# PDU.net
KiCad netlist of a schematic drawn in Altium Designer
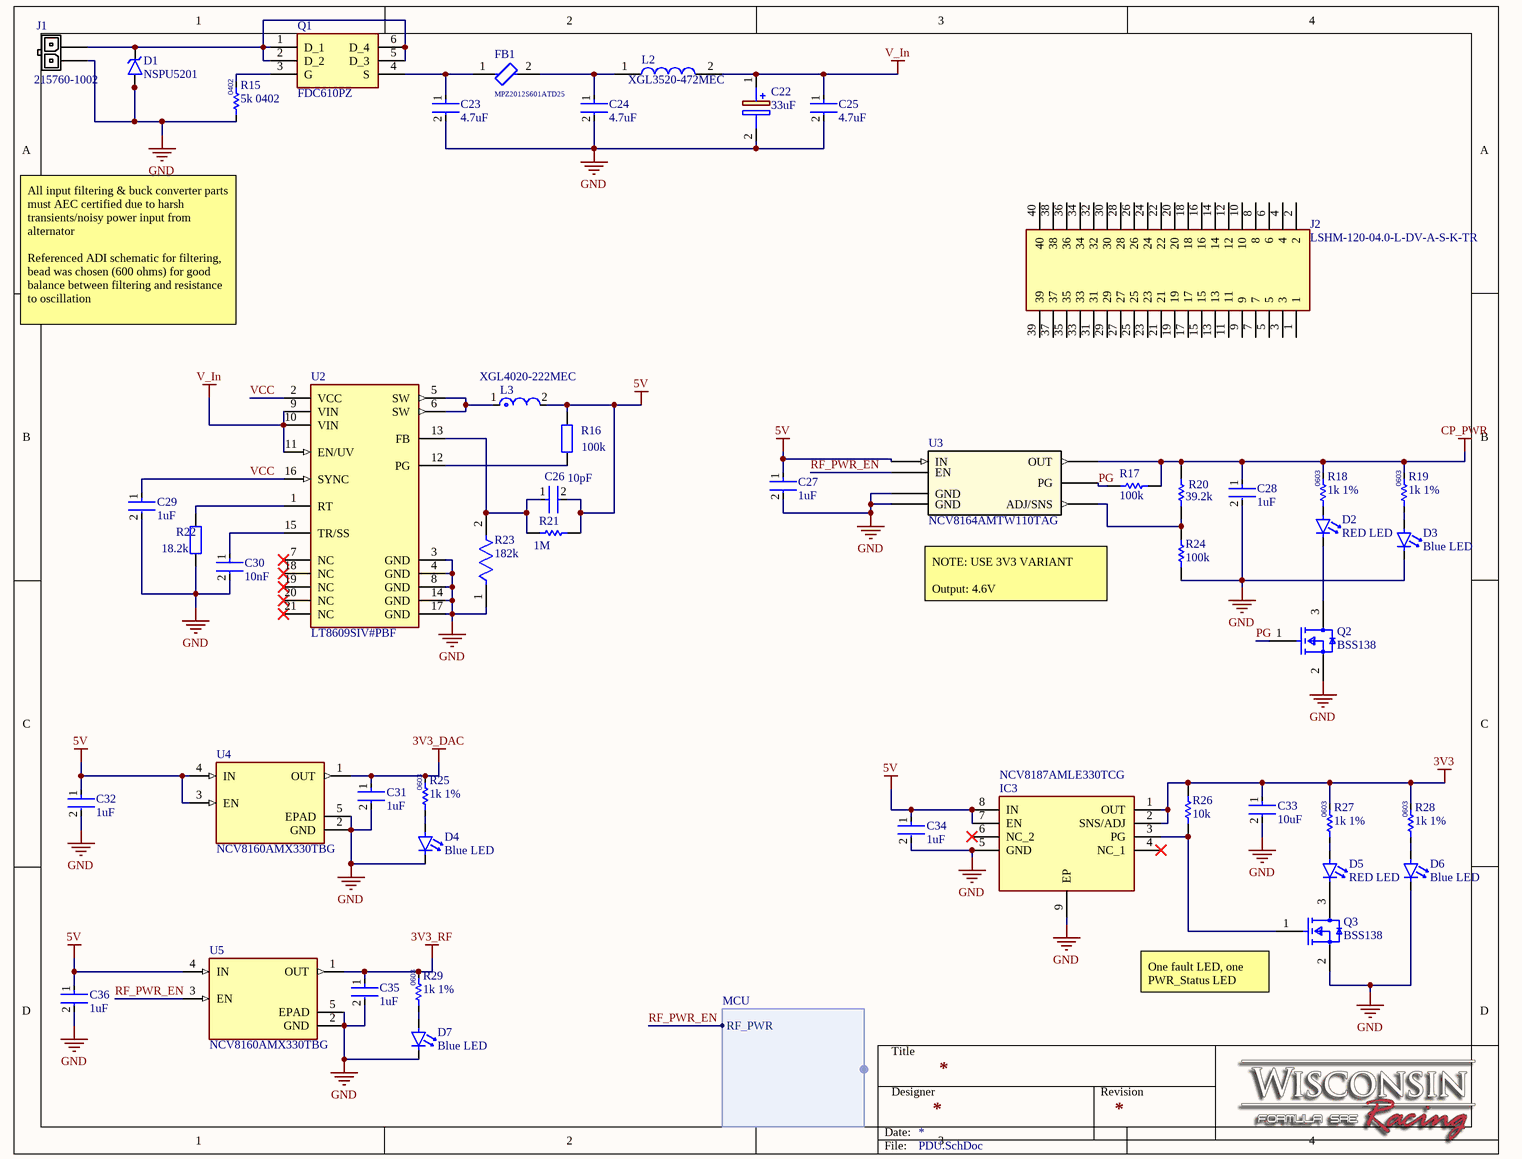
[diagram p0: PDU.SchDoc]

(export (version "E")
  (design (tool "Eeschema 10.0.6"))
  (components
    (comp (ref "C22")
      (value "33uF")
      (footprint "SamacSys:MAL215097904E3")
      (description "Capacitor Polarised\r\n\r\nMAL215097904E3")
      (fields
        (field (name "MANUFACTURER_PART_NUMBER") "MAL215097904E3")
        (field (name "MOUSER PART NUMBER") "594-MAL215097904E3")
      )
      (libsource (lib "*") (part "MAL215097904E3"))
    )
    (comp (ref "C23")
      (value "4.7uF")
      (footprint "FP-CGA4J-IPC_C")
      (description "Cap Ceramic 4.7uF 50V X7R 10% Pad SMD 0805 +125°C Automotive T/R")
      (libsource (lib "Altium Content Vault") (part "b4654b650e69147ec39a6b967a45e02"))
    )
    (comp (ref "C24")
      (value "4.7uF")
      (footprint "FP-CGA4J-IPC_C")
      (description "Cap Ceramic 4.7uF 50V X7R 10% Pad SMD 0805 +125°C Automotive T/R")
      (libsource (lib "Altium Content Vault") (part "b4654b650e69147ec39a6b967a45e02"))
    )
    (comp (ref "C25")
      (value "4.7uF")
      (footprint "FP-CGA4J-IPC_C")
      (description "Cap Ceramic 4.7uF 50V X7R 10% Pad SMD 0805 +125°C Automotive T/R")
      (libsource (lib "Altium Content Vault") (part "b4654b650e69147ec39a6b967a45e02"))
    )
    (comp (ref "C26")
      (value "10pF")
      (footprint "FP-GCM155-0_05-IPC_C")
      (description "Ceramic Capacitor for Automotive 10pF ±5% 50VDC C0G 0402 Paper T/R")
      (fields (field (name "TOLERANCE") "5%"))
      (libsource (lib "Altium Content Vault") (part "02cd4be3c70576c341d710602a673aa"))
    )
    (comp (ref "C27")
      (value "1uF")
      (footprint "FP-GRM155-0_1-IPC_C")
      (libsource (lib "Altium Content Vault") (part "11868f565c42a9108669ba33697ecf6"))
    )
    (comp (ref "C28")
      (value "1uF")
      (footprint "FP-GRM155-0_1-IPC_C")
      (libsource (lib "Altium Content Vault") (part "11868f565c42a9108669ba33697ecf6"))
    )
    (comp (ref "C29")
      (value "1uF")
      (footprint "FP-GRT155-0_1-IPC_A")
      (description "Multi-Layer Ceramic Capacitor 1uF 25V X6S ±10% 0402 Paper T/R\r\n\r\nGRT155C81E105KE13D")
      (libsource (lib "Altium Content Vault") (part "02cd4be3c70576c341d710602a673aa"))
    )
    (comp (ref "C30")
      (value "10nF")
      (footprint "FP-GCM155-0_05-IPC_C")
      (description "Ceramic Capacitor for Automotive 10nF ±10% 50VDC X7R 0402 Paper T/R\r\n\r\nGCM155R71H103KA55D")
      (fields (field (name "TOLERANCE") "10%") (field (name "VOLTAGE") "50V"))
      (libsource (lib "Altium Content Vault") (part "02cd4be3c70576c341d710602a673aa"))
    )
    (comp (ref "C31")
      (value "1uF")
      (footprint "FP-GRM155-0_1-IPC_C")
      (libsource (lib "Altium Content Vault") (part "11868f565c42a9108669ba33697ecf6"))
    )
    (comp (ref "C32")
      (value "1uF")
      (footprint "FP-GRM155-0_1-IPC_C")
      (libsource (lib "Altium Content Vault") (part "11868f565c42a9108669ba33697ecf6"))
    )
    (comp (ref "C33")
      (value "10uF")
      (footprint "FP-GRM155-0_2-IPC_A")
      (description "Chip Multilayer Ceramic Capacitors for General Purpose, 0402, 10uF, X5R, 15%, 20%, 6.3V")
      (libsource (lib "Altium Content Vault") (part "b4654b650e69147ec39a6b967a45e02"))
    )
    (comp (ref "C34")
      (value "1uF")
      (footprint "FP-GRM155-0_1-IPC_C")
      (libsource (lib "Altium Content Vault") (part "11868f565c42a9108669ba33697ecf6"))
    )
    (comp (ref "C35")
      (value "1uF")
      (footprint "FP-GRM155-0_1-IPC_C")
      (libsource (lib "Altium Content Vault") (part "11868f565c42a9108669ba33697ecf6"))
    )
    (comp (ref "C36")
      (value "1uF")
      (footprint "FP-GRM155-0_1-IPC_C")
      (libsource (lib "Altium Content Vault") (part "11868f565c42a9108669ba33697ecf6"))
    )
    (comp (ref "D1")
      (value "NSPU5201")
      (footprint "NSPM5131MUTBG")
      (fields
        (field (name "ARROW PART NUMBER") "NSPU5201MUTBG")
        (field (name "MOUSER PART NUMBER") "863-NSPU5201MUTBG")
      )
      (libsource (lib "University of Wisconsin Formula FSAE") (part "NSPU5201MUTBG"))
    )
    (comp (ref "D2")
      (value "RED LED")
      (footprint "DIOC1608X05N")
      (description "0603 Red SMD Led")
      (libsource (lib "University of Wisconsin Formula FSAE") (part "L196L-LIC-Symbol-1"))
    )
    (comp (ref "D3")
      (value "Blue LED")
      (footprint "0603-LED-1")
      (description "Single Color LED, Blue, Water Clear, 1.1mm")
      (libsource (lib "University of Wisconsin Formula FSAE") (part "LED"))
    )
    (comp (ref "D4")
      (value "Blue LED")
      (footprint "0603-LED-1")
      (description "Single Color LED, Blue, Water Clear, 1.1mm")
      (libsource (lib "University of Wisconsin Formula FSAE") (part "LED"))
    )
    (comp (ref "D5")
      (value "RED LED")
      (footprint "DIOC1608X05N")
      (description "0603 Red SMD Led")
      (libsource (lib "University of Wisconsin Formula FSAE") (part "L196L-LIC-Symbol-1"))
    )
    (comp (ref "D6")
      (value "Blue LED")
      (footprint "0603-LED-1")
      (description "Single Color LED, Blue, Water Clear, 1.1mm")
      (libsource (lib "University of Wisconsin Formula FSAE") (part "LED"))
    )
    (comp (ref "D7")
      (value "Blue LED")
      (footprint "0603-LED-1")
      (description "Single Color LED, Blue, Water Clear, 1.1mm")
      (libsource (lib "University of Wisconsin Formula FSAE") (part "LED"))
    )
    (comp (ref "FB1")
      (value "MPZ2012S601ATD25")
      (footprint "BEADC2012X105N")
      (description "Ferrite Beads Multi-Layer Power 600Ohm 25% 100MHz 2A 100mOhm DCR 0805 Automotive T/R")
      (fields (field (name "MOUSER PART NUMBER") "810-MPZ2012S601ATD25"))
      (libsource (lib "University of Wisconsin Formula FSAE") (part "MPZ2012S601ATD25"))
    )
    (comp (ref "IC3")
      (value "NCV8187AMLE330TCG")
      (footprint "SamacSys:SON65P300X300X100-9N-D")
      (description "Integrated Circuit")
      (fields (field (name "MOUSER PART NUMBER") "863-CV8187AMLE330TCG"))
      (libsource (lib "*") (part "NCV8187AMLE330TCG"))
    )
    (comp (ref "J1")
      (value "215760-1002")
      (footprint "215760-1002-Footprint-1")
      (libsource (lib "University of Wisconsin Formula FSAE") (part "961102-6404-AR"))
    )
    (comp (ref "J2")
      (value "LSHM-120-04.0-L-DV-A-S-K-TR")
      (footprint "SamacSys:LSHM-120-XX.X-YYY-DV-A-S-K-TR")
      (description "Connector")
      (fields (field (name "MOUSER PART NUMBER") "200-LSHM12004LDVASK"))
      (libsource (lib "*") (part "LSHM-120-04.0-L-DV-A-S-K-TR"))
    )
    (comp (ref "L2")
      (value "XGL3520-472MEC")
      (footprint "SamacSys:XGL3520472MEC")
      (description "Inductor")
      (libsource (lib "*") (part "XGL3520-472MEC"))
    )
    (comp (ref "L3")
      (value "XGL4020-222MEC")
      (footprint "FP-XGL4020-MFG")
      (description "Shielded Power Inductors")
      (libsource (lib "Altium Content Vault") (part "4cc4b267dca4c8e51f7102f422741d8"))
    )
    (comp (ref "Q1")
      (value "FDC610PZ")
      (footprint "SamacSys:SOT95P280X110-6N")
      (description "MOSFET (P-Channel)")
      (fields (field (name "MOUSER PART NUMBER") "512-FDC610PZ"))
      (libsource (lib "*") (part "FDC610PZ"))
    )
    (comp (ref "Q2")
      (value "BSS138")
      (footprint "FP-318-08-IPC_B")
      (description "MOSFET N-CH 50V 220MA SOT-23")
      (libsource (lib "Altium Content Vault") (part "3b9c635fedb024a5347a57b145af9cc"))
    )
    (comp (ref "Q3")
      (value "BSS138")
      (footprint "FP-318-08-IPC_B")
      (description "MOSFET N-CH 50V 220MA SOT-23")
      (libsource (lib "Altium Content Vault") (part "3b9c635fedb024a5347a57b145af9cc"))
    )
    (comp (ref "R15")
      (value "5k 0402")
      (footprint "Res0402-Type-1")
      (fields (field (name "TOLERANCE") "1%") (field (name "POWER") "63mW"))
      (libsource (lib "University of Wisconsin Formula FSAE") (part "RES"))
    )
    (comp (ref "R16")
      (value "100k")
      (footprint "WRIS-RSKS_0402")
      (description "Resistor, 100K, 0.1W, Thick Film, 0402 Rohs Compliant: Yes")
      (libsource (lib "Altium Content Vault") (part "Resistor"))
    )
    (comp (ref "R17")
      (value "100k")
      (footprint "RESC1005X40X25NL05T10")
      (fields (field (name "PART NUMBER") "RC0402FR-07100KL") (field (name "MANUFACTURER") "Yageo / Phycomp"))
      (libsource (lib "Altium Content Vault") (part "RES"))
    )
    (comp (ref "R18")
      (value "1k 1%")
      (footprint "Res0603-type-1")
      (libsource (lib "University of Wisconsin Formula FSAE") (part "RES 0603"))
    )
    (comp (ref "R19")
      (value "1k 1%")
      (footprint "Res0603-type-1")
      (libsource (lib "University of Wisconsin Formula FSAE") (part "RES 0603"))
    )
    (comp (ref "R20")
      (value "39.2k")
      (footprint "RESC1005X40X25ML05T10")
      (fields (field (name "PART NUMBER") "RC0402FR-0739K2L") (field (name "MANUFACTURER") "Yageo"))
      (libsource (lib "Altium Content Vault") (part "RES"))
    )
    (comp (ref "R21")
      (value "1M")
      (footprint "RESC1005X40X25NL05T10")
      (fields (field (name "MANUFACTURER") "Yageo / Phycomp") (field (name "PART NUMBER") "RC0402FR-071ML"))
      (libsource (lib "Altium Content Vault") (part "RES"))
    )
    (comp (ref "R22")
      (value "18.2k")
      (footprint "WRIS-RSKS_0402")
      (description "Resistor, 18K2, 0.1W, Thick Film, 0402 Rohs Compliant: Yes")
      (libsource (lib "Altium Content Vault") (part "Resistor"))
    )
    (comp (ref "R23")
      (value "182k")
      (footprint "FP-AC0402-IPC_C")
      (description "RES 182kΩ ±1% 0.063W 0402")
      (fields (field (name "TOLERANCE") "1%"))
      (libsource (lib "Altium Content Vault") (part "1029c3af85768c4190bb7ad29bc67b5"))
    )
    (comp (ref "R24")
      (value "100k")
      (footprint "RESC1005X40X25NL05T10")
      (fields (field (name "PART NUMBER") "RC0402FR-07100KL") (field (name "MANUFACTURER") "Yageo / Phycomp"))
      (libsource (lib "Altium Content Vault") (part "RES"))
    )
    (comp (ref "R25")
      (value "1k 1%")
      (footprint "Res0603-type-1")
      (libsource (lib "University of Wisconsin Formula FSAE") (part "RES 0603"))
    )
    (comp (ref "R26")
      (value "10k")
      (footprint "RESC1005X40X25ML05T05")
      (fields (field (name "PART NUMBER") "ERJ-2GEJ103X") (field (name "MANUFACTURER") "Panasonic"))
      (libsource (lib "Altium Content Vault") (part "RES"))
    )
    (comp (ref "R27")
      (value "1k 1%")
      (footprint "Res0603-type-1")
      (libsource (lib "University of Wisconsin Formula FSAE") (part "RES 0603"))
    )
    (comp (ref "R28")
      (value "1k 1%")
      (footprint "Res0603-type-1")
      (libsource (lib "University of Wisconsin Formula FSAE") (part "RES 0603"))
    )
    (comp (ref "R29")
      (value "1k 1%")
      (footprint "Res0603-type-1")
      (libsource (lib "University of Wisconsin Formula FSAE") (part "RES 0603"))
    )
    (comp (ref "U2")
      (value "LT8609SIV#PBF")
      (footprint "FP-LQFN-16-05-08-1516-MFG")
      (description "IC REG BUCK ADJUSTABLE 2A 16LQFN")
      (fields
        (field (name "OCTOPART") "https://octopart.com/lt8609siv%23pbf-analog+devices-88316701")
        (field (name "MANUFACTURER") "Analog Devices")
      )
      (libsource (lib "Altium Content Vault") (part "5cdaaed650003e075ab076d5d3b68d5"))
    )
    (comp (ref "U3")
      (value "NCV8164AMTW110TAG")
      (footprint "WDFNW6_511DW_OSI")
      (description "LDO")
      (fields (field (name "COPYRIGHT") "Copyright (C) 2025 Ultra Librarian. All rights reserved."))
      (libsource (lib "University of Wisconsin Formula FSAE") (part "NCV8164AMTW110TAG"))
    )
    (comp (ref "U4")
      (value "NCV8160AMX330TBG")
      (footprint "VREG_NCV8160AMX330TBG")
      (description "Linear Voltage Regulator IC Positive Fixed 1 Output 250mA 4-XDFN (1x1)")
      (fields (field (name "MF") "ON Semiconductor"))
      (libsource (lib "University of Wisconsin Formula FSAE") (part "NCV8160AMX330TBG"))
    )
    (comp (ref "U5")
      (value "NCV8160AMX330TBG")
      (footprint "VREG_NCV8160AMX330TBG")
      (description "Linear Voltage Regulator IC Positive Fixed 1 Output 250mA 4-XDFN (1x1)")
      (fields (field (name "MF") "ON Semiconductor"))
      (libsource (lib "University of Wisconsin Formula FSAE") (part "NCV8160AMX330TBG"))
    )
  )
  (nets
    (net (code "1") (name "/PG") (class "Default")
      (node (ref "Q2") (pin "1") (pinfunction "G_1") (pintype "passive"))
      (node (ref "R17") (pin "2") (pinfunction "2_2") (pintype "passive"))
      (node (ref "U3") (pin "3") (pinfunction "PG_3") (pintype "passive"))
    )
    (net (code "2") (name "/RF_PWR_EN") (class "Default")
      (node (ref "U3") (pin "4") (pinfunction "EN_4") (pintype "passive"))
      (node (ref "U5") (pin "3") (pinfunction "EN_3") (pintype "input"))
    )
    (net (code "3") (name "/VCC") (class "Default")
      (node (ref "C29") (pin "1") (pinfunction "1_1") (pintype "passive"))
      (node (ref "U2") (pin "16") (pinfunction "SYNC_16") (pintype "input"))
      (node (ref "U2") (pin "2") (pinfunction "VCC_2") (pintype "power_in"))
    )
    (net (code "4") (name "3V3") (class "Default")
      (node (ref "C33") (pin "1") (pinfunction "1_1") (pintype "passive"))
      (node (ref "IC3") (pin "1") (pinfunction "OUT_1") (pintype "passive"))
      (node (ref "IC3") (pin "2") (pinfunction "SNS/ADJ_2") (pintype "passive"))
      (node (ref "R26") (pin "2") (pinfunction "2_2") (pintype "passive"))
      (node (ref "R27") (pin "2") (pinfunction "2_2") (pintype "passive"))
      (node (ref "R28") (pin "2") (pinfunction "2_2") (pintype "passive"))
    )
    (net (code "5") (name "3V3_DAC") (class "Default")
      (node (ref "C31") (pin "1") (pinfunction "1_1") (pintype "passive"))
      (node (ref "R25") (pin "2") (pinfunction "2_2") (pintype "passive"))
      (node (ref "U4") (pin "1") (pinfunction "OUT_1") (pintype "output"))
    )
    (net (code "6") (name "3V3_RF") (class "Default")
      (node (ref "C35") (pin "1") (pinfunction "1_1") (pintype "passive"))
      (node (ref "R29") (pin "2") (pinfunction "2_2") (pintype "passive"))
      (node (ref "U5") (pin "1") (pinfunction "OUT_1") (pintype "output"))
    )
    (net (code "7") (name "5V") (class "Default")
      (node (ref "C26") (pin "2") (pinfunction "2_2") (pintype "passive"))
      (node (ref "C27") (pin "1") (pinfunction "1_1") (pintype "passive"))
      (node (ref "C32") (pin "1") (pinfunction "1_1") (pintype "passive"))
      (node (ref "C34") (pin "1") (pinfunction "1_1") (pintype "passive"))
      (node (ref "C36") (pin "1") (pinfunction "1_1") (pintype "passive"))
      (node (ref "IC3") (pin "7") (pinfunction "EN_7") (pintype "passive"))
      (node (ref "IC3") (pin "8") (pinfunction "IN_8") (pintype "passive"))
      (node (ref "L3") (pin "2") (pinfunction "2_2") (pintype "passive"))
      (node (ref "R16") (pin "2") (pinfunction "2_2") (pintype "passive"))
      (node (ref "R21") (pin "2") (pinfunction "2_2") (pintype "passive"))
      (node (ref "U3") (pin "6") (pinfunction "IN_6") (pintype "input"))
      (node (ref "U4") (pin "3") (pinfunction "EN_3") (pintype "input"))
      (node (ref "U4") (pin "4") (pinfunction "IN_4") (pintype "input"))
      (node (ref "U5") (pin "4") (pinfunction "IN_4") (pintype "input"))
    )
    (net (code "8") (name "CP_PWR") (class "Default")
      (node (ref "C28") (pin "1") (pinfunction "1_1") (pintype "passive"))
      (node (ref "R17") (pin "1") (pinfunction "1_1") (pintype "passive"))
      (node (ref "R18") (pin "2") (pinfunction "2_2") (pintype "passive"))
      (node (ref "R19") (pin "2") (pinfunction "2_2") (pintype "passive"))
      (node (ref "R20") (pin "2") (pinfunction "2_2") (pintype "passive"))
      (node (ref "U3") (pin "1") (pinfunction "OUT_1") (pintype "output"))
    )
    (net (code "9") (name "GND") (class "Default")
      (node (ref "C22") (pin "2") (pinfunction "-_2") (pintype "passive"))
      (node (ref "C23") (pin "2") (pinfunction "2_2") (pintype "passive"))
      (node (ref "C24") (pin "2") (pinfunction "2_2") (pintype "passive"))
      (node (ref "C25") (pin "2") (pinfunction "2_2") (pintype "passive"))
      (node (ref "C27") (pin "2") (pinfunction "2_2") (pintype "passive"))
      (node (ref "C28") (pin "2") (pinfunction "2_2") (pintype "passive"))
      (node (ref "C29") (pin "2") (pinfunction "2_2") (pintype "passive"))
      (node (ref "C30") (pin "2") (pinfunction "2_2") (pintype "passive"))
      (node (ref "C31") (pin "2") (pinfunction "2_2") (pintype "passive"))
      (node (ref "C32") (pin "2") (pinfunction "2_2") (pintype "passive"))
      (node (ref "C33") (pin "2") (pinfunction "2_2") (pintype "passive"))
      (node (ref "C34") (pin "2") (pinfunction "2_2") (pintype "passive"))
      (node (ref "C35") (pin "2") (pinfunction "2_2") (pintype "passive"))
      (node (ref "C36") (pin "2") (pinfunction "2_2") (pintype "passive"))
      (node (ref "D1") (pin "5") (pinfunction "GND_(A)_1_5") (pintype "passive"))
      (node (ref "D1") (pin "6") (pinfunction "GND_(A)_2_6") (pintype "passive"))
      (node (ref "D1") (pin "7") (pinfunction "GND_(A)_3_7") (pintype "passive"))
      (node (ref "D1") (pin "8") (pinfunction "GND_(A)_4_8") (pintype "passive"))
      (node (ref "D3") (pin "1") (pinfunction "C_1") (pintype "passive"))
      (node (ref "D4") (pin "1") (pinfunction "C_1") (pintype "passive"))
      (node (ref "D6") (pin "1") (pinfunction "C_1") (pintype "passive"))
      (node (ref "D7") (pin "1") (pinfunction "C_1") (pintype "passive"))
      (node (ref "IC3") (pin "5") (pinfunction "GND_5") (pintype "passive"))
      (node (ref "IC3") (pin "9") (pinfunction "EP_9") (pintype "passive"))
      (node (ref "J1") (pin "2") (pinfunction "2_2") (pintype "passive"))
      (node (ref "Q2") (pin "2") (pinfunction "S_2") (pintype "passive"))
      (node (ref "Q3") (pin "2") (pinfunction "S_2") (pintype "passive"))
      (node (ref "R15") (pin "1") (pinfunction "1_1") (pintype "passive"))
      (node (ref "R22") (pin "1") (pinfunction "1_1") (pintype "passive"))
      (node (ref "R23") (pin "1") (pinfunction "1_1") (pintype "passive"))
      (node (ref "R24") (pin "1") (pinfunction "1_1") (pintype "passive"))
      (node (ref "U2") (pin "14") (pinfunction "GND_14") (pintype "power_in"))
      (node (ref "U2") (pin "17") (pinfunction "GND_17") (pintype "power_in"))
      (node (ref "U2") (pin "3") (pinfunction "GND_3") (pintype "power_in"))
      (node (ref "U2") (pin "4") (pinfunction "GND_4") (pintype "power_in"))
      (node (ref "U2") (pin "8") (pinfunction "GND_8") (pintype "power_in"))
      (node (ref "U3") (pin "5") (pinfunction "GND_5") (pintype "power_in"))
      (node (ref "U3") (pin "7") (pinfunction "GND_7") (pintype "power_in"))
      (node (ref "U4") (pin "2") (pinfunction "GND_2") (pintype "power_in"))
      (node (ref "U4") (pin "5") (pinfunction "EPAD_5") (pintype "power_in"))
      (node (ref "U5") (pin "2") (pinfunction "GND_2") (pintype "power_in"))
      (node (ref "U5") (pin "5") (pinfunction "EPAD_5") (pintype "power_in"))
    )
    (net (code "10") (name "Net-(C24-Pad1)") (class "Default")
      (node (ref "C24") (pin "1") (pinfunction "1_1") (pintype "passive"))
      (node (ref "FB1") (pin "2") (pinfunction "2_2") (pintype "passive"))
      (node (ref "L2") (pin "1") (pinfunction "1_1") (pintype "passive"))
    )
    (net (code "11") (name "Net-(D2-C)") (class "Default")
      (node (ref "D2") (pin "1") (pinfunction "C_1") (pintype "passive"))
      (node (ref "Q2") (pin "3") (pinfunction "D_3") (pintype "passive"))
    )
    (net (code "12") (name "Net-(D3-A)") (class "Default")
      (node (ref "D3") (pin "2") (pinfunction "A_2") (pintype "passive"))
      (node (ref "R19") (pin "1") (pinfunction "1_1") (pintype "passive"))
    )
    (net (code "13") (name "Net-(D4-A)") (class "Default")
      (node (ref "D4") (pin "2") (pinfunction "A_2") (pintype "passive"))
      (node (ref "R25") (pin "1") (pinfunction "1_1") (pintype "passive"))
    )
    (net (code "14") (name "Net-(D5-A)") (class "Default")
      (node (ref "D5") (pin "2") (pinfunction "A_2") (pintype "passive"))
      (node (ref "R27") (pin "1") (pinfunction "1_1") (pintype "passive"))
    )
    (net (code "15") (name "Net-(D5-C)") (class "Default")
      (node (ref "D5") (pin "1") (pinfunction "C_1") (pintype "passive"))
      (node (ref "Q3") (pin "3") (pinfunction "D_3") (pintype "passive"))
    )
    (net (code "16") (name "Net-(D6-A)") (class "Default")
      (node (ref "D6") (pin "2") (pinfunction "A_2") (pintype "passive"))
      (node (ref "R28") (pin "1") (pinfunction "1_1") (pintype "passive"))
    )
    (net (code "17") (name "Net-(D7-A)") (class "Default")
      (node (ref "D7") (pin "2") (pinfunction "A_2") (pintype "passive"))
      (node (ref "R29") (pin "1") (pinfunction "1_1") (pintype "passive"))
    )
    (net (code "18") (name "Net-(IC3-PG)") (class "Default")
      (node (ref "IC3") (pin "3") (pinfunction "PG_3") (pintype "passive"))
      (node (ref "Q3") (pin "1") (pinfunction "G_1") (pintype "passive"))
      (node (ref "R26") (pin "1") (pinfunction "1_1") (pintype "passive"))
    )
    (net (code "19") (name "Net-(L3-Pad1)") (class "Default")
      (node (ref "L3") (pin "1") (pinfunction "1_1") (pintype "passive"))
      (node (ref "U2") (pin "5") (pinfunction "SW_5") (pintype "output"))
      (node (ref "U2") (pin "6") (pinfunction "SW_6") (pintype "output"))
    )
    (net (code "20") (name "Net-(Q1-D_1)") (class "Default")
      (node (ref "D1") (pin "1") (pinfunction "1_1") (pintype "passive"))
      (node (ref "D1") (pin "2") (pinfunction "2_2") (pintype "passive"))
      (node (ref "J1") (pin "1") (pinfunction "1_1") (pintype "passive"))
      (node (ref "Q1") (pin "1") (pinfunction "D_1_1") (pintype "passive"))
      (node (ref "Q1") (pin "2") (pinfunction "D_2_2") (pintype "passive"))
      (node (ref "Q1") (pin "5") (pinfunction "D_3_5") (pintype "passive"))
      (node (ref "Q1") (pin "6") (pinfunction "D_4_6") (pintype "passive"))
    )
    (net (code "21") (name "Net-(Q1-G)") (class "Default")
      (node (ref "Q1") (pin "3") (pinfunction "G_3") (pintype "passive"))
      (node (ref "R15") (pin "2") (pinfunction "2_2") (pintype "passive"))
    )
    (net (code "22") (name "Net-(Q1-S)") (class "Default")
      (node (ref "C23") (pin "1") (pinfunction "1_1") (pintype "passive"))
      (node (ref "FB1") (pin "1") (pinfunction "1_1") (pintype "passive"))
      (node (ref "Q1") (pin "4") (pinfunction "S_4") (pintype "passive"))
    )
    (net (code "23") (name "Net-(U2-FB)") (class "Default")
      (node (ref "C26") (pin "1") (pinfunction "1_1") (pintype "passive"))
      (node (ref "R21") (pin "1") (pinfunction "1_1") (pintype "passive"))
      (node (ref "R23") (pin "2") (pinfunction "2_2") (pintype "passive"))
      (node (ref "U2") (pin "13") (pinfunction "FB_13") (pintype "passive"))
    )
    (net (code "24") (name "Net-(U2-PG)") (class "Default")
      (node (ref "R16") (pin "1") (pinfunction "1_1") (pintype "passive"))
      (node (ref "U2") (pin "12") (pinfunction "PG_12") (pintype "open_collector"))
    )
    (net (code "25") (name "Net-(U2-RT)") (class "Default")
      (node (ref "R22") (pin "2") (pinfunction "2_2") (pintype "passive"))
      (node (ref "U2") (pin "1") (pinfunction "RT_1") (pintype "passive"))
    )
    (net (code "26") (name "Net-(U2-TR{slash}SS)") (class "Default")
      (node (ref "C30") (pin "1") (pinfunction "1_1") (pintype "passive"))
      (node (ref "U2") (pin "15") (pinfunction "TR/SS_15") (pintype "passive"))
    )
    (net (code "27") (name "Net-(U3-ADJ{slash}SNS)") (class "Default")
      (node (ref "R20") (pin "1") (pinfunction "1_1") (pintype "passive"))
      (node (ref "R24") (pin "2") (pinfunction "2_2") (pintype "passive"))
      (node (ref "U3") (pin "2") (pinfunction "ADJ/SNS_2") (pintype "output"))
    )
    (net (code "28") (name "V_In") (class "Default")
      (node (ref "C22") (pin "1") (pinfunction "+_1") (pintype "passive"))
      (node (ref "C25") (pin "1") (pinfunction "1_1") (pintype "passive"))
      (node (ref "L2") (pin "2") (pinfunction "2_2") (pintype "passive"))
      (node (ref "U2") (pin "10") (pinfunction "VIN_10") (pintype "power_in"))
      (node (ref "U2") (pin "11") (pinfunction "EN/UV_11") (pintype "input"))
      (node (ref "U2") (pin "9") (pinfunction "VIN_9") (pintype "power_in"))
    )
    (net (code "29") (name "unconnected-(D2-A-Pad2)") (class "Default")
      (node (ref "D2") (pin "2") (pinfunction "A_2") (pintype "passive"))
    )
    (net (code "30") (name "unconnected-(IC3-NC_1-Pad4)") (class "Default")
      (node (ref "IC3") (pin "4") (pinfunction "NC_1_4") (pintype "passive+no_connect"))
    )
    (net (code "31") (name "unconnected-(IC3-NC_2-Pad6)") (class "Default")
      (node (ref "IC3") (pin "6") (pinfunction "NC_2_6") (pintype "passive+no_connect"))
    )
    (net (code "32") (name "unconnected-(J2-Pad1)") (class "Default")
      (node (ref "J2") (pin "1") (pinfunction "1_1") (pintype "passive"))
    )
    (net (code "33") (name "unconnected-(J2-Pad2)") (class "Default")
      (node (ref "J2") (pin "2") (pinfunction "2_2") (pintype "passive"))
    )
    (net (code "34") (name "unconnected-(J2-Pad3)") (class "Default")
      (node (ref "J2") (pin "3") (pinfunction "3_3") (pintype "passive"))
    )
    (net (code "35") (name "unconnected-(J2-Pad4)") (class "Default")
      (node (ref "J2") (pin "4") (pinfunction "4_4") (pintype "passive"))
    )
    (net (code "36") (name "unconnected-(J2-Pad5)") (class "Default")
      (node (ref "J2") (pin "5") (pinfunction "5_5") (pintype "passive"))
    )
    (net (code "37") (name "unconnected-(J2-Pad6)") (class "Default")
      (node (ref "J2") (pin "6") (pinfunction "6_6") (pintype "passive"))
    )
    (net (code "38") (name "unconnected-(J2-Pad7)") (class "Default")
      (node (ref "J2") (pin "7") (pinfunction "7_7") (pintype "passive"))
    )
    (net (code "39") (name "unconnected-(J2-Pad8)") (class "Default")
      (node (ref "J2") (pin "8") (pinfunction "8_8") (pintype "passive"))
    )
    (net (code "40") (name "unconnected-(J2-Pad9)") (class "Default")
      (node (ref "J2") (pin "9") (pinfunction "9_9") (pintype "passive"))
    )
    (net (code "41") (name "unconnected-(J2-Pad10)") (class "Default")
      (node (ref "J2") (pin "10") (pinfunction "10_10") (pintype "passive"))
    )
    (net (code "42") (name "unconnected-(J2-Pad11)") (class "Default")
      (node (ref "J2") (pin "11") (pinfunction "11_11") (pintype "passive"))
    )
    (net (code "43") (name "unconnected-(J2-Pad12)") (class "Default")
      (node (ref "J2") (pin "12") (pinfunction "12_12") (pintype "passive"))
    )
    (net (code "44") (name "unconnected-(J2-Pad13)") (class "Default")
      (node (ref "J2") (pin "13") (pinfunction "13_13") (pintype "passive"))
    )
    (net (code "45") (name "unconnected-(J2-Pad14)") (class "Default")
      (node (ref "J2") (pin "14") (pinfunction "14_14") (pintype "passive"))
    )
    (net (code "46") (name "unconnected-(J2-Pad15)") (class "Default")
      (node (ref "J2") (pin "15") (pinfunction "15_15") (pintype "passive"))
    )
    (net (code "47") (name "unconnected-(J2-Pad16)") (class "Default")
      (node (ref "J2") (pin "16") (pinfunction "16_16") (pintype "passive"))
    )
    (net (code "48") (name "unconnected-(J2-Pad17)") (class "Default")
      (node (ref "J2") (pin "17") (pinfunction "17_17") (pintype "passive"))
    )
    (net (code "49") (name "unconnected-(J2-Pad18)") (class "Default")
      (node (ref "J2") (pin "18") (pinfunction "18_18") (pintype "passive"))
    )
    (net (code "50") (name "unconnected-(J2-Pad19)") (class "Default")
      (node (ref "J2") (pin "19") (pinfunction "19_19") (pintype "passive"))
    )
    (net (code "51") (name "unconnected-(J2-Pad20)") (class "Default")
      (node (ref "J2") (pin "20") (pinfunction "20_20") (pintype "passive"))
    )
    (net (code "52") (name "unconnected-(J2-Pad21)") (class "Default")
      (node (ref "J2") (pin "21") (pinfunction "21_21") (pintype "passive"))
    )
    (net (code "53") (name "unconnected-(J2-Pad22)") (class "Default")
      (node (ref "J2") (pin "22") (pinfunction "22_22") (pintype "passive"))
    )
    (net (code "54") (name "unconnected-(J2-Pad23)") (class "Default")
      (node (ref "J2") (pin "23") (pinfunction "23_23") (pintype "passive"))
    )
    (net (code "55") (name "unconnected-(J2-Pad24)") (class "Default")
      (node (ref "J2") (pin "24") (pinfunction "24_24") (pintype "passive"))
    )
    (net (code "56") (name "unconnected-(J2-Pad25)") (class "Default")
      (node (ref "J2") (pin "25") (pinfunction "25_25") (pintype "passive"))
    )
    (net (code "57") (name "unconnected-(J2-Pad26)") (class "Default")
      (node (ref "J2") (pin "26") (pinfunction "26_26") (pintype "passive"))
    )
    (net (code "58") (name "unconnected-(J2-Pad27)") (class "Default")
      (node (ref "J2") (pin "27") (pinfunction "27_27") (pintype "passive"))
    )
    (net (code "59") (name "unconnected-(J2-Pad28)") (class "Default")
      (node (ref "J2") (pin "28") (pinfunction "28_28") (pintype "passive"))
    )
    (net (code "60") (name "unconnected-(J2-Pad29)") (class "Default")
      (node (ref "J2") (pin "29") (pinfunction "29_29") (pintype "passive"))
    )
    (net (code "61") (name "unconnected-(J2-Pad30)") (class "Default")
      (node (ref "J2") (pin "30") (pinfunction "30_30") (pintype "passive"))
    )
    (net (code "62") (name "unconnected-(J2-Pad31)") (class "Default")
      (node (ref "J2") (pin "31") (pinfunction "31_31") (pintype "passive"))
    )
    (net (code "63") (name "unconnected-(J2-Pad32)") (class "Default")
      (node (ref "J2") (pin "32") (pinfunction "32_32") (pintype "passive"))
    )
    (net (code "64") (name "unconnected-(J2-Pad33)") (class "Default")
      (node (ref "J2") (pin "33") (pinfunction "33_33") (pintype "passive"))
    )
    (net (code "65") (name "unconnected-(J2-Pad34)") (class "Default")
      (node (ref "J2") (pin "34") (pinfunction "34_34") (pintype "passive"))
    )
    (net (code "66") (name "unconnected-(J2-Pad35)") (class "Default")
      (node (ref "J2") (pin "35") (pinfunction "35_35") (pintype "passive"))
    )
    (net (code "67") (name "unconnected-(J2-Pad36)") (class "Default")
      (node (ref "J2") (pin "36") (pinfunction "36_36") (pintype "passive"))
    )
    (net (code "68") (name "unconnected-(J2-Pad37)") (class "Default")
      (node (ref "J2") (pin "37") (pinfunction "37_37") (pintype "passive"))
    )
    (net (code "69") (name "unconnected-(J2-Pad38)") (class "Default")
      (node (ref "J2") (pin "38") (pinfunction "38_38") (pintype "passive"))
    )
    (net (code "70") (name "unconnected-(J2-Pad39)") (class "Default")
      (node (ref "J2") (pin "39") (pinfunction "39_39") (pintype "passive"))
    )
    (net (code "71") (name "unconnected-(J2-Pad40)") (class "Default")
      (node (ref "J2") (pin "40") (pinfunction "40_40") (pintype "passive"))
    )
    (net (code "72") (name "unconnected-(R18-Pad1)") (class "Default")
      (node (ref "R18") (pin "1") (pinfunction "1_1") (pintype "passive"))
    )
    (net (code "73") (name "unconnected-(U2-NC-Pad7)") (class "Default")
      (node (ref "U2") (pin "7") (pinfunction "NC_7") (pintype "passive+no_connect"))
    )
    (net (code "74") (name "unconnected-(U2-NC-Pad18)") (class "Default")
      (node (ref "U2") (pin "18") (pinfunction "NC_18") (pintype "passive+no_connect"))
    )
    (net (code "75") (name "unconnected-(U2-NC-Pad19)") (class "Default")
      (node (ref "U2") (pin "19") (pinfunction "NC_19") (pintype "passive+no_connect"))
    )
    (net (code "76") (name "unconnected-(U2-NC-Pad20)") (class "Default")
      (node (ref "U2") (pin "20") (pinfunction "NC_20") (pintype "passive+no_connect"))
    )
    (net (code "77") (name "unconnected-(U2-NC-Pad21)") (class "Default")
      (node (ref "U2") (pin "21") (pinfunction "NC_21") (pintype "passive+no_connect"))
    )
  )
)
